# Phase_Measurements.net
KiCad netlist of a schematic drawn in Altium Designer
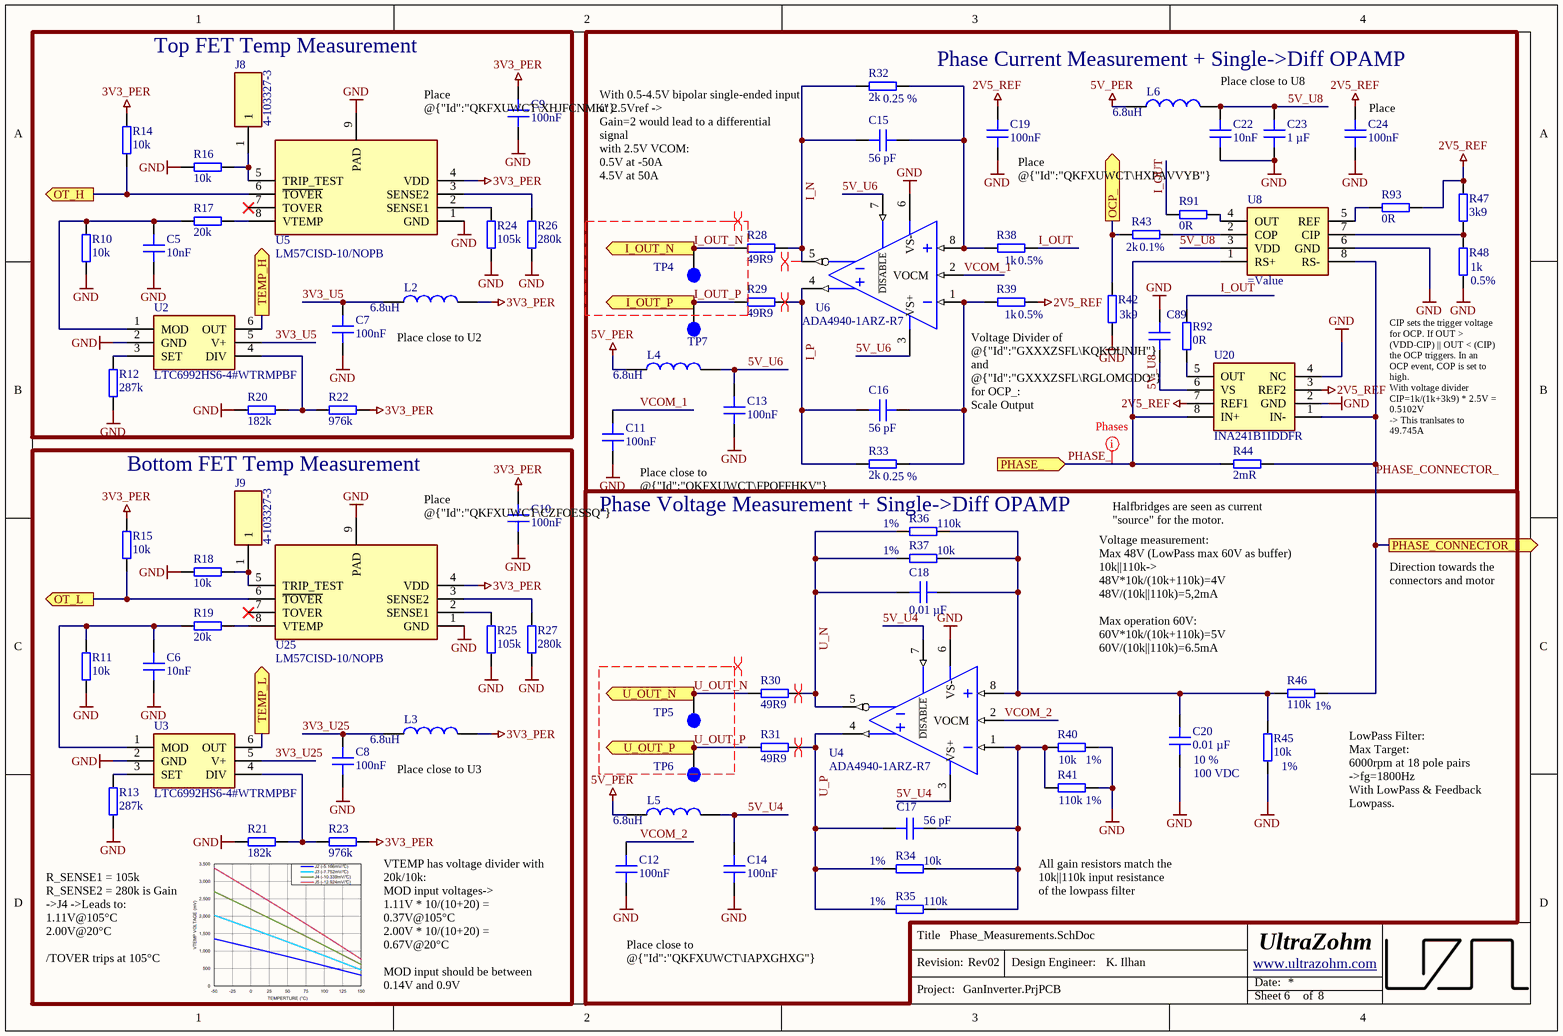
[diagram p0: Phase_Measurements.SchDoc]

(export (version "E")
  (design (tool "Eeschema 10.0.6"))
  (components
    (comp (ref "C5")
      (value "10nF")
      (footprint "C_0603")
      (description "50V 10nF 2X1 ±10%")
      (fields
        (field (name "MANUFACTURER PART NUMBER") "CT41G-0603-2X1-50V-0.01μF-K(N)")
        (field (name "MANUFACTURER") "TORCH")
        (field (name "CREATED FROM") "KIlhan")
      )
      (libsource (lib "user") (part "Capacitor"))
    )
    (comp (ref "C6")
      (value "10nF")
      (footprint "C_0603")
      (description "50V 10nF 2X1 ±10%")
      (fields
        (field (name "MANUFACTURER PART NUMBER") "CT41G-0603-2X1-50V-0.01μF-K(N)")
        (field (name "MANUFACTURER") "TORCH")
        (field (name "CREATED FROM") "KIlhan")
      )
      (libsource (lib "user") (part "Capacitor"))
    )
    (comp (ref "C7")
      (value "100nF")
      (footprint "C_0603")
      (description "50V 100nF X8R ±10% 0603")
      (fields
        (field (name "MANUFACTURER PART NUMBER") "CGA3E3X8R1H104KT0Y0N")
        (field (name "MANUFACTURER") "TDK")
        (field (name "CREATED FROM") "KIlhan")
      )
      (libsource (lib "user") (part "Capacitor"))
    )
    (comp (ref "C8")
      (value "100nF")
      (footprint "C_0603")
      (description "50V 100nF X8R ±10% 0603")
      (fields
        (field (name "MANUFACTURER PART NUMBER") "CGA3E3X8R1H104KT0Y0N")
        (field (name "MANUFACTURER") "TDK")
        (field (name "CREATED FROM") "KIlhan")
      )
      (libsource (lib "user") (part "Capacitor"))
    )
    (comp (ref "C9")
      (value "100nF")
      (footprint "C_0603")
      (description "50V 100nF X8R ±10% 0603")
      (fields
        (field (name "MANUFACTURER PART NUMBER") "CGA3E3X8R1H104KT0Y0N")
        (field (name "MANUFACTURER") "TDK")
        (field (name "CREATED FROM") "KIlhan")
      )
      (libsource (lib "user") (part "Capacitor"))
    )
    (comp (ref "C10")
      (value "100nF")
      (footprint "C_0603")
      (description "50V 100nF X8R ±10% 0603")
      (fields
        (field (name "MANUFACTURER PART NUMBER") "CGA3E3X8R1H104KT0Y0N")
        (field (name "MANUFACTURER") "TDK")
        (field (name "CREATED FROM") "KIlhan")
      )
      (libsource (lib "user") (part "Capacitor"))
    )
    (comp (ref "C11")
      (value "100nF")
      (footprint "C_0603")
      (description "50V 100nF X8R ±10% 0603")
      (fields
        (field (name "MANUFACTURER PART NUMBER") "CGA3E3X8R1H104KT0Y0N")
        (field (name "MANUFACTURER") "TDK")
        (field (name "CREATED FROM") "KIlhan")
      )
      (libsource (lib "user") (part "Capacitor"))
    )
    (comp (ref "C12")
      (value "100nF")
      (footprint "C_0603")
      (description "50V 100nF X8R ±10% 0603")
      (fields
        (field (name "MANUFACTURER PART NUMBER") "CGA3E3X8R1H104KT0Y0N")
        (field (name "MANUFACTURER") "TDK")
        (field (name "CREATED FROM") "KIlhan")
      )
      (libsource (lib "user") (part "Capacitor"))
    )
    (comp (ref "C13")
      (value "100nF")
      (footprint "C_0603")
      (description "50V 100nF X8R ±10% 0603")
      (fields
        (field (name "MANUFACTURER PART NUMBER") "CGA3E3X8R1H104KT0Y0N")
        (field (name "MANUFACTURER") "TDK")
        (field (name "CREATED FROM") "KIlhan")
      )
      (libsource (lib "user") (part "Capacitor"))
    )
    (comp (ref "C14")
      (value "100nF")
      (footprint "C_0603")
      (description "50V 100nF X8R ±10% 0603")
      (fields
        (field (name "MANUFACTURER PART NUMBER") "CGA3E3X8R1H104KT0Y0N")
        (field (name "MANUFACTURER") "TDK")
        (field (name "CREATED FROM") "KIlhan")
      )
      (libsource (lib "user") (part "Capacitor"))
    )
    (comp (ref "C15")
      (value "56 pF")
      (footprint "C_0603")
      (description "Capacitor 0603, 50 VDC, 56 pF, C0G")
      (fields
        (field (name "MANUFACTURER PART NUMBER") "CL10C560JB8NNNC")
        (field (name "MANUFACTURER") "Samsung Electro-Mechanics")
        (field (name "CREATED FROM") "DHufnagel")
      )
      (libsource (lib "user") (part "Capacitor"))
    )
    (comp (ref "C16")
      (value "56 pF")
      (footprint "C_0603")
      (description "Capacitor 0603, 50 VDC, 56 pF, C0G")
      (fields
        (field (name "MANUFACTURER PART NUMBER") "CL10C560JB8NNNC")
        (field (name "MANUFACTURER") "Samsung Electro-Mechanics")
        (field (name "CREATED FROM") "DHufnagel")
      )
      (libsource (lib "user") (part "Capacitor"))
    )
    (comp (ref "C17")
      (value "56 pF")
      (footprint "C_0603")
      (description "Capacitor 0603, 50 VDC, 56 pF, C0G")
      (fields
        (field (name "MANUFACTURER PART NUMBER") "CL10C560JB8NNNC")
        (field (name "MANUFACTURER") "Samsung Electro-Mechanics")
        (field (name "CREATED FROM") "DHufnagel")
      )
      (libsource (lib "user") (part "Capacitor"))
    )
    (comp (ref "C18")
      (value "0.01 µF")
      (footprint "C_0603")
      (description "25V 10nF C0G ±5% 0603 Multilayer Ceramic Capacitors MLCC - SMD/SMT ROHS")
      (fields
        (field (name "MANUFACTURER PART NUMBER") "C1608C0G1E103JT000N")
        (field (name "MANUFACTURER") "TDK")
        (field (name "CREATED FROM") "KIlhan")
      )
      (libsource (lib "user") (part "Capacitor"))
    )
    (comp (ref "C19")
      (value "100nF")
      (footprint "C_0603")
      (description "50V 100nF X8R ±10% 0603")
      (fields
        (field (name "MANUFACTURER PART NUMBER") "CGA3E3X8R1H104KT0Y0N")
        (field (name "MANUFACTURER") "TDK")
        (field (name "CREATED FROM") "KIlhan")
      )
      (libsource (lib "user") (part "Capacitor"))
    )
    (comp (ref "C20")
      (value "0.01 µF")
      (footprint "C_0805")
      (description "100V 10nF 0805 Multilayer Ceramic Capacitors MLCC - SMD/SMT ROHS")
      (fields
        (field (name "MANUFACTURER PART NUMBER") "HV0805X7R103K101NT")
        (field (name "MANUFACTURER") "AIDE")
        (field (name "TOLERANCE") "10 %")
        (field (name "VOLTAGE RATING") "100 VDC")
        (field (name "CREATED FROM") "KIlhan")
      )
      (libsource (lib "user") (part "Capacitor"))
    )
    (comp (ref "C22")
      (value "10nF")
      (footprint "C_0603")
      (description "50V 10nF 2X1 ±10%")
      (fields
        (field (name "MANUFACTURER PART NUMBER") "CT41G-0603-2X1-50V-0.01μF-K(N)")
        (field (name "MANUFACTURER") "TORCH")
        (field (name "CREATED FROM") "KIlhan")
      )
      (libsource (lib "user") (part "Capacitor"))
    )
    (comp (ref "C23")
      (value "1 µF")
      (footprint "C_0603")
      (description "50V 1uF X7R ±10% 0603 Multilayer Ceramic Capacitors MLCC - SMD/SMT ROHS")
      (fields
        (field (name "MANUFACTURER PART NUMBER") "UMK107AB7105KA-T")
        (field (name "MANUFACTURER") "Taiyo Yuden")
        (field (name "CREATED FROM") "NDiringer")
      )
      (libsource (lib "user") (part "Capacitor"))
    )
    (comp (ref "C24")
      (value "100nF")
      (footprint "C_0603")
      (description "50V 100nF X8R ±10% 0603")
      (fields
        (field (name "MANUFACTURER PART NUMBER") "CGA3E3X8R1H104KT0Y0N")
        (field (name "MANUFACTURER") "TDK")
        (field (name "CREATED FROM") "KIlhan")
      )
      (libsource (lib "user") (part "Capacitor"))
    )
    (comp (ref "C89")
      (value "100 nF")
      (footprint "C_0603")
      (description "Capacitor 0603, 50 VDC, 100 nF, X7R")
      (fields
        (field (name "MANUFACTURER PART NUMBER") "CC0603KRX7R9BB104")
        (field (name "MANUFACTURER") "YAGEO")
        (field (name "CREATED FROM") "AGeiger")
      )
      (libsource (lib "user") (part "Capacitor"))
    )
    (comp (ref "J8")
      (value "4-103327-3")
      (footprint "1_Pin_Header")
      (description "Pin Header, 2.54mm, 1 Pin")
      (fields
        (field (name "MANUFACTURER") "TE Connectivity")
        (field (name "LCSC PART NUMBER") "C3347196")
        (field (name "CREATED FROM") "DHufnagel")
      )
      (libsource (lib "user") (part "4-103327-3"))
    )
    (comp (ref "J9")
      (value "4-103327-3")
      (footprint "1_Pin_Header")
      (description "Pin Header, 2.54mm, 1 Pin")
      (fields
        (field (name "MANUFACTURER") "TE Connectivity")
        (field (name "LCSC PART NUMBER") "C3347196")
        (field (name "CREATED FROM") "DHufnagel")
      )
      (libsource (lib "user") (part "4-103327-3"))
    )
    (comp (ref "L2")
      (value "6.8uH")
      (footprint "INDC1608X95N")
      (description "6.8uH ±10% 0603 Inductors (SMD) ROHS")
      (fields
        (field (name "MF") "EPCOS / TDK")
        (field (name "MPN") "B82464G4154M")
        (field (name "CREATED FROM") "KIlhan")
      )
      (libsource (lib "user") (part "B82464G4154M"))
    )
    (comp (ref "L3")
      (value "6.8uH")
      (footprint "INDC1608X95N")
      (description "6.8uH ±10% 0603 Inductors (SMD) ROHS")
      (fields
        (field (name "MF") "EPCOS / TDK")
        (field (name "MPN") "B82464G4154M")
        (field (name "CREATED FROM") "KIlhan")
      )
      (libsource (lib "user") (part "B82464G4154M"))
    )
    (comp (ref "L4")
      (value "6.8uH")
      (footprint "INDC1608X95N")
      (description "6.8uH ±10% 0603 Inductors (SMD) ROHS")
      (fields
        (field (name "MF") "EPCOS / TDK")
        (field (name "MPN") "B82464G4154M")
        (field (name "CREATED FROM") "KIlhan")
      )
      (libsource (lib "user") (part "B82464G4154M"))
    )
    (comp (ref "L5")
      (value "6.8uH")
      (footprint "INDC1608X95N")
      (description "6.8uH ±10% 0603 Inductors (SMD) ROHS")
      (fields
        (field (name "MF") "EPCOS / TDK")
        (field (name "MPN") "B82464G4154M")
        (field (name "CREATED FROM") "KIlhan")
      )
      (libsource (lib "user") (part "B82464G4154M"))
    )
    (comp (ref "L6")
      (value "6.8uH")
      (footprint "INDC1608X95N")
      (description "6.8uH ±10% 0603 Inductors (SMD) ROHS")
      (fields
        (field (name "MF") "EPCOS / TDK")
        (field (name "MPN") "B82464G4154M")
        (field (name "CREATED FROM") "KIlhan")
      )
      (libsource (lib "user") (part "B82464G4154M"))
    )
    (comp (ref "R10")
      (value "10k")
      (footprint "RES 0603_1608")
      (description "SMD resistor E24 series")
      (fields
        (field (name "MANUFACTURER PART NUMBER") "RK73B1JTTD103J")
        (field (name "MANUFACTURER") "KOA Speer")
        (field (name "CREATED FROM") "MGremer")
      )
      (libsource (lib "user") (part "Resistor"))
    )
    (comp (ref "R11")
      (value "10k")
      (footprint "RES 0603_1608")
      (description "SMD resistor E24 series")
      (fields
        (field (name "MANUFACTURER PART NUMBER") "RK73B1JTTD103J")
        (field (name "MANUFACTURER") "KOA Speer")
        (field (name "CREATED FROM") "MGremer")
      )
      (libsource (lib "user") (part "Resistor"))
    )
    (comp (ref "R12")
      (value "287k")
      (footprint "RES 0805_2012")
      (description "SMD resistor 1%")
      (fields
        (field (name "MANUFACTURER PART NUMBER") "ERJ-6ENF2873V")
        (field (name "MANUFACTURER") "Panasonic")
        (field (name "CREATED FROM") "MGremer")
      )
      (libsource (lib "user") (part "Resistor"))
    )
    (comp (ref "R13")
      (value "287k")
      (footprint "RES 0805_2012")
      (description "SMD resistor 1%")
      (fields
        (field (name "MANUFACTURER PART NUMBER") "ERJ-6ENF2873V")
        (field (name "MANUFACTURER") "Panasonic")
        (field (name "CREATED FROM") "MGremer")
      )
      (libsource (lib "user") (part "Resistor"))
    )
    (comp (ref "R14")
      (value "10k")
      (footprint "RES 0603_1608")
      (description "SMD resistor E24 series")
      (fields
        (field (name "MANUFACTURER PART NUMBER") "RK73B1JTTD103J")
        (field (name "MANUFACTURER") "KOA Speer")
        (field (name "CREATED FROM") "MGremer")
      )
      (libsource (lib "user") (part "Resistor"))
    )
    (comp (ref "R15")
      (value "10k")
      (footprint "RES 0603_1608")
      (description "SMD resistor E24 series")
      (fields
        (field (name "MANUFACTURER PART NUMBER") "RK73B1JTTD103J")
        (field (name "MANUFACTURER") "KOA Speer")
        (field (name "CREATED FROM") "MGremer")
      )
      (libsource (lib "user") (part "Resistor"))
    )
    (comp (ref "R16")
      (value "10k")
      (footprint "RES 0603_1608")
      (description "SMD resistor E24 series")
      (fields
        (field (name "MANUFACTURER PART NUMBER") "RK73B1JTTD103J")
        (field (name "MANUFACTURER") "KOA Speer")
        (field (name "CREATED FROM") "MGremer")
      )
      (libsource (lib "user") (part "Resistor"))
    )
    (comp (ref "R17")
      (value "20k")
      (footprint "RES 0603_1608")
      (description "SMD resistor E24 series")
      (fields
        (field (name "MANUFACTURER PART NUMBER") "0603WAF2002T5E")
        (field (name "MANUFACTURER") "UNI-ROYAL")
        (field (name "CREATED FROM") "AGeiger")
      )
      (libsource (lib "user") (part "Resistor"))
    )
    (comp (ref "R18")
      (value "10k")
      (footprint "RES 0603_1608")
      (description "SMD resistor E24 series")
      (fields
        (field (name "MANUFACTURER PART NUMBER") "RK73B1JTTD103J")
        (field (name "MANUFACTURER") "KOA Speer")
        (field (name "CREATED FROM") "MGremer")
      )
      (libsource (lib "user") (part "Resistor"))
    )
    (comp (ref "R19")
      (value "20k")
      (footprint "RES 0603_1608")
      (description "SMD resistor E24 series")
      (fields
        (field (name "MANUFACTURER PART NUMBER") "0603WAF2002T5E")
        (field (name "MANUFACTURER") "UNI-ROYAL")
        (field (name "CREATED FROM") "AGeiger")
      )
      (libsource (lib "user") (part "Resistor"))
    )
    (comp (ref "R20")
      (value "182k")
      (footprint "RES 0603_1608")
      (description "SMD resistor 1%, 50V, 100ppm")
      (fields
        (field (name "MANUFACTURER PART NUMBER") "CR0603-FX-1823ELF")
        (field (name "MANUFACTURER") "Bourns")
        (field (name "CREATED FROM") "DHufnagel")
      )
      (libsource (lib "user") (part "Resistor"))
    )
    (comp (ref "R21")
      (value "182k")
      (footprint "RES 0603_1608")
      (description "SMD resistor 1%, 50V, 100ppm")
      (fields
        (field (name "MANUFACTURER PART NUMBER") "CR0603-FX-1823ELF")
        (field (name "MANUFACTURER") "Bourns")
        (field (name "CREATED FROM") "DHufnagel")
      )
      (libsource (lib "user") (part "Resistor"))
    )
    (comp (ref "R22")
      (value "976k")
      (footprint "RES 0603_1608")
      (description "SMD resistor 1%, 50V, 100ppm")
      (fields
        (field (name "MANUFACTURER PART NUMBER") "CR0603-FX-9763ELF")
        (field (name "MANUFACTURER") "Bourns")
        (field (name "CREATED FROM") "DHufnagel")
      )
      (libsource (lib "user") (part "Resistor"))
    )
    (comp (ref "R23")
      (value "976k")
      (footprint "RES 0603_1608")
      (description "SMD resistor 1%, 50V, 100ppm")
      (fields
        (field (name "MANUFACTURER PART NUMBER") "CR0603-FX-9763ELF")
        (field (name "MANUFACTURER") "Bourns")
        (field (name "CREATED FROM") "DHufnagel")
      )
      (libsource (lib "user") (part "Resistor"))
    )
    (comp (ref "R24")
      (value "105k")
      (footprint "RES 0603_1608")
      (description "100mW Thick Film Resistors ±100ppm/℃ ±1% 105kΩ 0603 Chip Resistor - Surface Mount ROHS")
      (fields
        (field (name "MANUFACTURER PART NUMBER") "RC0603FR-07105KL")
        (field (name "MANUFACTURER") "YAGEO")
        (field (name "CREATED FROM") "KIlhan")
      )
      (libsource (lib "user") (part "Resistor"))
    )
    (comp (ref "R25")
      (value "105k")
      (footprint "RES 0603_1608")
      (description "100mW Thick Film Resistors ±100ppm/℃ ±1% 105kΩ 0603 Chip Resistor - Surface Mount ROHS")
      (fields
        (field (name "MANUFACTURER PART NUMBER") "RC0603FR-07105KL")
        (field (name "MANUFACTURER") "YAGEO")
        (field (name "CREATED FROM") "KIlhan")
      )
      (libsource (lib "user") (part "Resistor"))
    )
    (comp (ref "R26")
      (value "280k")
      (footprint "RES 0603_1608")
      (description "100mW Thin Film Resistor ±50ppm/℃ ±0.1% 280kΩ 0603 Chip Resistor - Surface Mount ROHS")
      (fields
        (field (name "MANUFACTURER PART NUMBER") "RT0603BRE07280KL")
        (field (name "MANUFACTURER") "YAGEO")
        (field (name "CREATED FROM") "KIlhan")
      )
      (libsource (lib "user") (part "Resistor"))
    )
    (comp (ref "R27")
      (value "280k")
      (footprint "RES 0603_1608")
      (description "100mW Thin Film Resistor ±50ppm/℃ ±0.1% 280kΩ 0603 Chip Resistor - Surface Mount ROHS")
      (fields
        (field (name "MANUFACTURER PART NUMBER") "RT0603BRE07280KL")
        (field (name "MANUFACTURER") "YAGEO")
        (field (name "CREATED FROM") "KIlhan")
      )
      (libsource (lib "user") (part "Resistor"))
    )
    (comp (ref "R28")
      (value "49R9")
      (footprint "RES 0603_1608")
      (description "125mW Thin Film Resistor ±0.1% ±25ppm/℃ 49.9Ω 0603")
      (fields
        (field (name "MANUFACTURER PART NUMBER") "TNPW060349R9BEEA")
        (field (name "MANUFACTURER") "Vishay Intertech")
        (field (name "CREATED FROM") "KIlhan")
      )
      (libsource (lib "user") (part "Resistor"))
    )
    (comp (ref "R29")
      (value "49R9")
      (footprint "RES 0603_1608")
      (description "125mW Thin Film Resistor ±0.1% ±25ppm/℃ 49.9Ω 0603")
      (fields
        (field (name "MANUFACTURER PART NUMBER") "TNPW060349R9BEEA")
        (field (name "MANUFACTURER") "Vishay Intertech")
        (field (name "CREATED FROM") "KIlhan")
      )
      (libsource (lib "user") (part "Resistor"))
    )
    (comp (ref "R30")
      (value "49R9")
      (footprint "RES 0603_1608")
      (description "125mW Thin Film Resistor ±0.1% ±25ppm/℃ 49.9Ω 0603")
      (fields
        (field (name "MANUFACTURER PART NUMBER") "TNPW060349R9BEEA")
        (field (name "MANUFACTURER") "Vishay Intertech")
        (field (name "CREATED FROM") "KIlhan")
      )
      (libsource (lib "user") (part "Resistor"))
    )
    (comp (ref "R31")
      (value "49R9")
      (footprint "RES 0603_1608")
      (description "125mW Thin Film Resistor ±0.1% ±25ppm/℃ 49.9Ω 0603")
      (fields
        (field (name "MANUFACTURER PART NUMBER") "TNPW060349R9BEEA")
        (field (name "MANUFACTURER") "Vishay Intertech")
        (field (name "CREATED FROM") "KIlhan")
      )
      (libsource (lib "user") (part "Resistor"))
    )
    (comp (ref "R32")
      (value "2k")
      (footprint "RES 0603_1608")
      (description "100mW Thin Film Resistor ±50ppm/℃ ±0.25% 2kΩ 0603 Chip Resistor - Surface Mount ROHS")
      (fields
        (field (name "MANUFACTURER PART NUMBER") "RT0603CRE072KL")
        (field (name "MANUFACTURER") "YAGEO")
        (field (name "TOLERANCE") "0.25 %")
        (field (name "CREATED FROM") "KIlhan")
      )
      (libsource (lib "user") (part "Resistor"))
    )
    (comp (ref "R33")
      (value "2k")
      (footprint "RES 0603_1608")
      (description "100mW Thin Film Resistor ±50ppm/℃ ±0.25% 2kΩ 0603 Chip Resistor - Surface Mount ROHS")
      (fields
        (field (name "MANUFACTURER PART NUMBER") "RT0603CRE072KL")
        (field (name "MANUFACTURER") "YAGEO")
        (field (name "TOLERANCE") "0.25 %")
        (field (name "CREATED FROM") "KIlhan")
      )
      (libsource (lib "user") (part "Resistor"))
    )
    (comp (ref "R34")
      (value "10k")
      (footprint "RES 0603_1608")
      (description "SMD resistor 1%")
      (fields
        (field (name "MANUFACTURER PART NUMBER") "0603WAF1002T5E")
        (field (name "MANUFACTURER") "UNI-ROYAL")
        (field (name "TOLERANCE") "1%")
        (field (name "CREATED FROM") "AGeiger")
      )
      (libsource (lib "user") (part "Resistor"))
    )
    (comp (ref "R35")
      (value "110k")
      (footprint "RES 0603_1608")
      (description "100mW Thick Film Resistors ±100ppm/℃ ±1% 110kΩ 0603 Chip Resistor - Surface Mount ROHS")
      (fields
        (field (name "MANUFACTURER PART NUMBER") "WR06X1103FTL")
        (field (name "MANUFACTURER") "Walsin Tech Corp")
        (field (name "TOLERANCE") "1%")
        (field (name "CREATED FROM") "KIlhan")
      )
      (libsource (lib "user") (part "Resistor"))
    )
    (comp (ref "R36")
      (value "110k")
      (footprint "RES 0603_1608")
      (description "100mW Thick Film Resistors ±100ppm/℃ ±1% 110kΩ 0603 Chip Resistor - Surface Mount ROHS")
      (fields
        (field (name "MANUFACTURER PART NUMBER") "WR06X1103FTL")
        (field (name "MANUFACTURER") "Walsin Tech Corp")
        (field (name "TOLERANCE") "1%")
        (field (name "CREATED FROM") "KIlhan")
      )
      (libsource (lib "user") (part "Resistor"))
    )
    (comp (ref "R37")
      (value "10k")
      (footprint "RES 0603_1608")
      (description "SMD resistor 1%")
      (fields
        (field (name "MANUFACTURER PART NUMBER") "0603WAF1002T5E")
        (field (name "MANUFACTURER") "UNI-ROYAL")
        (field (name "TOLERANCE") "1%")
        (field (name "CREATED FROM") "AGeiger")
      )
      (libsource (lib "user") (part "Resistor"))
    )
    (comp (ref "R38")
      (value "1k")
      (footprint "RES 0603_1608")
      (description "SMD resistor E24 series 470 kOhms 100-200 mW 0603 1%")
      (fields
        (field (name "MANUFACTURER PART NUMBER") "0603WAD1001T5E")
        (field (name "MANUFACTURER") "UNI-ROYAL(Uniroyal Elec)")
        (field (name "TOLERANCE") "0.5%")
        (field (name "CREATED FROM") "NDiringer")
      )
      (libsource (lib "user") (part "Resistor"))
    )
    (comp (ref "R39")
      (value "1k")
      (footprint "RES 0603_1608")
      (description "SMD resistor E24 series 470 kOhms 100-200 mW 0603 1%")
      (fields
        (field (name "MANUFACTURER PART NUMBER") "0603WAD1001T5E")
        (field (name "MANUFACTURER") "UNI-ROYAL(Uniroyal Elec)")
        (field (name "TOLERANCE") "0.5%")
        (field (name "CREATED FROM") "NDiringer")
      )
      (libsource (lib "user") (part "Resistor"))
    )
    (comp (ref "R40")
      (value "10k")
      (footprint "RES 0603_1608")
      (description "SMD resistor 1%")
      (fields
        (field (name "MANUFACTURER PART NUMBER") "0603WAF1002T5E")
        (field (name "MANUFACTURER") "UNI-ROYAL")
        (field (name "TOLERANCE") "1%")
        (field (name "CREATED FROM") "AGeiger")
      )
      (libsource (lib "user") (part "Resistor"))
    )
    (comp (ref "R41")
      (value "110k")
      (footprint "RES 0603_1608")
      (description "100mW Thick Film Resistors ±100ppm/℃ ±1% 110kΩ 0603 Chip Resistor - Surface Mount ROHS")
      (fields
        (field (name "MANUFACTURER PART NUMBER") "WR06X1103FTL")
        (field (name "MANUFACTURER") "Walsin Tech Corp")
        (field (name "TOLERANCE") "1%")
        (field (name "CREATED FROM") "KIlhan")
      )
      (libsource (lib "user") (part "Resistor"))
    )
    (comp (ref "R42")
      (value "3k9")
      (footprint "RES 0603_1608")
      (description "SMD resistor E24 series")
      (fields
        (field (name "MANUFACTURER PART NUMBER") "RT0603FRE073K9L")
        (field (name "MANUFACTURER") "YAGEO")
        (field (name "CREATED FROM") "DHufnagel")
      )
      (libsource (lib "user") (part "Resistor"))
    )
    (comp (ref "R43")
      (value "2k")
      (footprint "RES 0603_1608")
      (description "SMD resistor 0.1%")
      (fields
        (field (name "MANUFACTURER PART NUMBER") "ERJ-PB3B2001V")
        (field (name "MANUFACTURER") "Panasonic")
        (field (name "TOLERANCE") "0.1%")
        (field (name "CREATED FROM") "DHufnagel")
      )
      (libsource (lib "user") (part "Resistor"))
    )
    (comp (ref "R44")
      (value "2mR")
      (footprint "3921")
      (description "Shunt resistor 2mOhm, 5W, 1%")
      (fields
        (field (name "MANUFACTURER PART NUMBER") "PU3921FKMP50R002L")
        (field (name "MANUFACTURER") "YAGEO")
        (field (name "CREATED FROM") "DHufnagel")
      )
      (libsource (lib "user") (part "Resistor"))
    )
    (comp (ref "R45")
      (value "10k")
      (footprint "RES 0603_1608")
      (description "SMD resistor 1%")
      (fields
        (field (name "MANUFACTURER PART NUMBER") "0603WAF1002T5E")
        (field (name "MANUFACTURER") "UNI-ROYAL")
        (field (name "TOLERANCE") "1%")
        (field (name "CREATED FROM") "AGeiger")
      )
      (libsource (lib "user") (part "Resistor"))
    )
    (comp (ref "R46")
      (value "110k")
      (footprint "RES 0603_1608")
      (description "100mW Thick Film Resistors ±100ppm/℃ ±1% 110kΩ 0603 Chip Resistor - Surface Mount ROHS")
      (fields
        (field (name "MANUFACTURER PART NUMBER") "WR06X1103FTL")
        (field (name "MANUFACTURER") "Walsin Tech Corp")
        (field (name "TOLERANCE") "1%")
        (field (name "CREATED FROM") "KIlhan")
      )
      (libsource (lib "user") (part "Resistor"))
    )
    (comp (ref "R47")
      (value "3k9")
      (footprint "RES 0603_1608")
      (description "SMD resistor E24 series")
      (fields
        (field (name "MANUFACTURER PART NUMBER") "RT0603FRE073K9L")
        (field (name "MANUFACTURER") "YAGEO")
        (field (name "CREATED FROM") "DHufnagel")
      )
      (libsource (lib "user") (part "Resistor"))
    )
    (comp (ref "R48")
      (value "1k")
      (footprint "RES 0603_1608")
      (description "SMD resistor E24 series 470 kOhms 100-200 mW 0603 1%")
      (fields
        (field (name "MANUFACTURER PART NUMBER") "0603WAD1001T5E")
        (field (name "MANUFACTURER") "UNI-ROYAL(Uniroyal Elec)")
        (field (name "TOLERANCE") "0.5%")
        (field (name "CREATED FROM") "NDiringer")
      )
      (libsource (lib "user") (part "Resistor"))
    )
    (comp (ref "R91")
      (value "0R")
      (footprint "RES 0603_1608")
      (description "SMD resistor E24 series")
      (fields
        (field (name "MANUFACTURER PART NUMBER") "RC0603JR-070RL")
        (field (name "MANUFACTURER") "YAGEO")
        (field (name "CREATED FROM") "MGremer")
      )
      (libsource (lib "user") (part "Resistor"))
    )
    (comp (ref "R92")
      (value "0R")
      (footprint "RES 0603_1608")
      (description "SMD resistor E24 series")
      (fields
        (field (name "MANUFACTURER PART NUMBER") "RC0603JR-070RL")
        (field (name "MANUFACTURER") "YAGEO")
        (field (name "CREATED FROM") "MGremer")
      )
      (libsource (lib "user") (part "Resistor"))
    )
    (comp (ref "R93")
      (value "0R")
      (footprint "RES 0603_1608")
      (description "SMD resistor E24 series")
      (fields
        (field (name "MANUFACTURER PART NUMBER") "RC0603JR-070RL")
        (field (name "MANUFACTURER") "YAGEO")
        (field (name "CREATED FROM") "MGremer")
      )
      (libsource (lib "user") (part "Resistor"))
    )
    (comp (ref "TP4")
      (value "Testpoint 1mm")
      (footprint "TP_1mm")
      (fields
        (field (name "MANUFACTURER PART NUMBER") "NULL")
        (field (name "CREATED") "2018_06_25_AGeiger")
        (field (name "CREATED FROM") "AGeiger")
      )
      (libsource (lib "user") (part "TP_1mm"))
    )
    (comp (ref "TP5")
      (value "Testpoint 1mm")
      (footprint "TP_1mm")
      (fields
        (field (name "MANUFACTURER PART NUMBER") "NULL")
        (field (name "CREATED") "2018_06_25_AGeiger")
        (field (name "CREATED FROM") "AGeiger")
      )
      (libsource (lib "user") (part "TP_1mm"))
    )
    (comp (ref "TP6")
      (value "Testpoint 1mm")
      (footprint "TP_1mm")
      (fields
        (field (name "MANUFACTURER PART NUMBER") "NULL")
        (field (name "CREATED") "2018_06_25_AGeiger")
        (field (name "CREATED FROM") "AGeiger")
      )
      (libsource (lib "user") (part "TP_1mm"))
    )
    (comp (ref "TP7")
      (value "Testpoint 1mm")
      (footprint "TP_1mm")
      (fields
        (field (name "MANUFACTURER PART NUMBER") "NULL")
        (field (name "CREATED") "2018_06_25_AGeiger")
        (field (name "CREATED FROM") "AGeiger")
      )
      (libsource (lib "user") (part "TP_1mm"))
    )
    (comp (ref "U2")
      (value "LTC6992HS6-4#WTRMPBF")
      (footprint "SOT95P280X100-6N")
      (description "Switching Controllers PWM with 5% to 100% Pulse Width Control")
      (fields
        (field (name "MANUFACTURER") "Analog Devices")
        (field (name "LCSC PART NUMBER") "C3304518")
        (field (name "CREATED FROM") "DHufnagel")
      )
      (libsource (lib "user") (part "LTC6992HS6-4#WTRMPBF"))
    )
    (comp (ref "U3")
      (value "LTC6992HS6-4#WTRMPBF")
      (footprint "SOT95P280X100-6N")
      (description "Switching Controllers PWM with 5% to 100% Pulse Width Control")
      (fields
        (field (name "MANUFACTURER") "Analog Devices")
        (field (name "LCSC PART NUMBER") "C3304518")
        (field (name "CREATED FROM") "DHufnagel")
      )
      (libsource (lib "user") (part "LTC6992HS6-4#WTRMPBF"))
    )
    (comp (ref "U4")
      (value "ADA4940-1ARZ-R7")
      (footprint "SOT127P600X175-8N")
      (description "Fully Differential Amplifier, Ultralow-Power,Low Distortion, 260-MHz")
      (fields
        (field (name "MANUFACTURER") "Analog Devices")
        (field (name "LCSC PART NUMBER") "C730049")
        (field (name "CREATED FROM") "DHufnagel")
      )
      (libsource (lib "user") (part "ADA4940-1ARZ"))
    )
    (comp (ref "U5")
      (value "LM57CISD-10/NOPB")
      (footprint "SON50P250X250X80-9N")
      (description "Board Mount Temperature Sensor, -50 - 150°C")
      (fields
        (field (name "MANUFACTURER") "Texas Instruments")
        (field (name "LCSC PART NUMBER") "C2864091")
        (field (name "CREATED FROM") "DHufnagel")
      )
      (libsource (lib "user") (part "LM57CISD-10_NOPB"))
    )
    (comp (ref "U6")
      (value "ADA4940-1ARZ-R7")
      (footprint "SOT127P600X175-8N")
      (description "Fully Differential Amplifier, Ultralow-Power,Low Distortion, 260-MHz")
      (fields
        (field (name "MANUFACTURER") "Analog Devices")
        (field (name "LCSC PART NUMBER") "C730049")
        (field (name "CREATED FROM") "DHufnagel")
      )
      (libsource (lib "user") (part "ADA4940-1ARZ"))
    )
    (comp (ref "U8")
      (value "~")
      (footprint "SOP65P490X110-8N")
      (description "Current Sense Amplifier, 300kHz, -0.1V to 65V CMV, 2 Channel")
      (fields
        (field (name "MANUFACTURER_PART_NUMBER") "MAX40056TAUA+")
        (field (name "MOUSER PART NUMBER") "700-MAX40056TAUA+")
        (field (name "CREATED FROM") "KIlhan")
      )
      (libsource (lib "user") (part "MAX40056TAUA+"))
    )
    (comp (ref "U20")
      (value "INA241B1IDDFR")
      (footprint "SOT65P280X110-8N")
      (fields
        (field (name "MOUSER PART NUMBER") "595-INA241B1IDDFR")
        (field (name "LCSC PART NUMBER") "C7433256")
        (field (name "MANUFACTURER") "Texas Instruments")
        (field (name "CREATED FROM") "KIlhan")
      )
      (libsource (lib "user") (part "INA241B1IDDFR"))
    )
    (comp (ref "U25")
      (value "LM57CISD-10/NOPB")
      (footprint "SON50P250X250X80-9N")
      (description "Board Mount Temperature Sensor, -50 - 150°C")
      (fields
        (field (name "MANUFACTURER") "Texas Instruments")
        (field (name "LCSC PART NUMBER") "C2864091")
        (field (name "CREATED FROM") "DHufnagel")
      )
      (libsource (lib "user") (part "LM57CISD-10_NOPB"))
    )
  )
  (nets
    (net (code "1") (name "/3V3_U5") (class "Default")
      (node (ref "C7") (pin "2") (pinfunction "2_2") (pintype "passive"))
      (node (ref "L2") (pin "1") (pinfunction "1_1") (pintype "passive"))
      (node (ref "U2") (pin "5") (pinfunction "V+_5") (pintype "passive"))
    )
    (net (code "2") (name "/3V3_U25") (class "Default")
      (node (ref "C8") (pin "2") (pinfunction "2_2") (pintype "passive"))
      (node (ref "L3") (pin "1") (pinfunction "1_1") (pintype "passive"))
      (node (ref "U3") (pin "5") (pinfunction "V+_5") (pintype "passive"))
    )
    (net (code "3") (name "/5V_U4") (class "Default")
      (node (ref "C14") (pin "2") (pinfunction "2_2") (pintype "passive"))
      (node (ref "L5") (pin "2") (pinfunction "2_2") (pintype "passive"))
      (node (ref "U4") (pin "3") (pinfunction "VS+_3") (pintype "power_in"))
      (node (ref "U4") (pin "7") (pinfunction "~{DISABLE}_7") (pintype "input"))
    )
    (net (code "4") (name "/5V_U6") (class "Default")
      (node (ref "C13") (pin "2") (pinfunction "2_2") (pintype "passive"))
      (node (ref "L4") (pin "2") (pinfunction "2_2") (pintype "passive"))
      (node (ref "U6") (pin "3") (pinfunction "VS+_3") (pintype "power_in"))
      (node (ref "U6") (pin "7") (pinfunction "~{DISABLE}_7") (pintype "input"))
    )
    (net (code "5") (name "/5V_U8") (class "Default")
      (node (ref "C22") (pin "2") (pinfunction "2_2") (pintype "passive"))
      (node (ref "C23") (pin "2") (pinfunction "2_2") (pintype "passive"))
      (node (ref "C89") (pin "2") (pinfunction "2_2") (pintype "passive"))
      (node (ref "L6") (pin "2") (pinfunction "2_2") (pintype "passive"))
      (node (ref "U20") (pin "6") (pinfunction "VS_6") (pintype "passive"))
      (node (ref "U8") (pin "3") (pinfunction "VDD_3") (pintype "passive"))
    )
    (net (code "6") (name "/I_N") (class "Default")
      (node (ref "C15") (pin "1") (pinfunction "1_1") (pintype "passive"))
      (node (ref "R28") (pin "2") (pinfunction "2_2") (pintype "passive"))
      (node (ref "R32") (pin "1") (pinfunction "1_1") (pintype "passive"))
      (node (ref "U6") (pin "5") (pinfunction "VOUT-_5") (pintype "output"))
    )
    (net (code "7") (name "/I_OUT") (class "Default")
      (node (ref "R38") (pin "2") (pinfunction "2_2") (pintype "passive"))
      (node (ref "R91") (pin "1") (pinfunction "1_1") (pintype "passive"))
      (node (ref "R92") (pin "2") (pinfunction "2_2") (pintype "passive"))
    )
    (net (code "8") (name "/I_OUT_N") (class "Default")
      (node (ref "R28") (pin "1") (pinfunction "1_1") (pintype "passive"))
      (node (ref "TP4") (pin "1") (pintype "passive"))
    )
    (net (code "9") (name "/I_OUT_P") (class "Default")
      (node (ref "R29") (pin "1") (pinfunction "1_1") (pintype "passive"))
      (node (ref "TP7") (pin "1") (pintype "passive"))
    )
    (net (code "10") (name "/I_P") (class "Default")
      (node (ref "C16") (pin "1") (pinfunction "1_1") (pintype "passive"))
      (node (ref "R29") (pin "2") (pinfunction "2_2") (pintype "passive"))
      (node (ref "R33") (pin "1") (pinfunction "1_1") (pintype "passive"))
      (node (ref "U6") (pin "4") (pinfunction "VOUT+_4") (pintype "output"))
    )
    (net (code "11") (name "/OCP_") (class "Default")
      (node (ref "R42") (pin "1") (pinfunction "1_1") (pintype "passive"))
      (node (ref "R43") (pin "1") (pinfunction "1_1") (pintype "passive"))
    )
    (net (code "12") (name "/OT_H") (class "Default")
      (node (ref "R14") (pin "2") (pinfunction "2_2") (pintype "passive"))
      (node (ref "U5") (pin "6") (pinfunction "~{TOVER}_6") (pintype "passive"))
    )
    (net (code "13") (name "/OT_L") (class "Default")
      (node (ref "R15") (pin "2") (pinfunction "2_2") (pintype "passive"))
      (node (ref "U25") (pin "6") (pinfunction "~{TOVER}_6") (pintype "passive"))
    )
    (net (code "14") (name "/PHASE_") (class "Default")
      (node (ref "R44") (pin "1") (pinfunction "1_1") (pintype "passive"))
      (node (ref "U20") (pin "8") (pinfunction "IN+_8") (pintype "passive"))
      (node (ref "U8") (pin "1") (pinfunction "RS+_1") (pintype "passive"))
    )
    (net (code "15") (name "/PHASE_CONNECTOR_") (class "Default")
      (node (ref "R44") (pin "2") (pinfunction "2_2") (pintype "passive"))
      (node (ref "R46") (pin "2") (pinfunction "2_2") (pintype "passive"))
      (node (ref "U20") (pin "1") (pinfunction "IN-_1") (pintype "passive"))
      (node (ref "U8") (pin "8") (pinfunction "RS-_8") (pintype "passive"))
    )
    (net (code "16") (name "/TEMP_H") (class "Default")
      (node (ref "U2") (pin "6") (pinfunction "OUT_6") (pintype "passive"))
    )
    (net (code "17") (name "/TEMP_L") (class "Default")
      (node (ref "U3") (pin "6") (pinfunction "OUT_6") (pintype "passive"))
    )
    (net (code "18") (name "/U_N") (class "Default")
      (node (ref "C18") (pin "1") (pinfunction "1_1") (pintype "passive"))
      (node (ref "R30") (pin "2") (pinfunction "2_2") (pintype "passive"))
      (node (ref "R36") (pin "1") (pinfunction "1_1") (pintype "passive"))
      (node (ref "R37") (pin "2") (pinfunction "2_2") (pintype "passive"))
      (node (ref "U4") (pin "5") (pinfunction "VOUT-_5") (pintype "output"))
    )
    (net (code "19") (name "/U_OUT_N") (class "Default")
      (node (ref "R30") (pin "1") (pinfunction "1_1") (pintype "passive"))
      (node (ref "TP5") (pin "1") (pintype "passive"))
    )
    (net (code "20") (name "/U_OUT_P") (class "Default")
      (node (ref "R31") (pin "1") (pinfunction "1_1") (pintype "passive"))
      (node (ref "TP6") (pin "1") (pintype "passive"))
    )
    (net (code "21") (name "/U_P") (class "Default")
      (node (ref "C17") (pin "1") (pinfunction "1_1") (pintype "passive"))
      (node (ref "R31") (pin "2") (pinfunction "2_2") (pintype "passive"))
      (node (ref "R34") (pin "2") (pinfunction "2_2") (pintype "passive"))
      (node (ref "R35") (pin "1") (pinfunction "1_1") (pintype "passive"))
      (node (ref "U4") (pin "4") (pinfunction "VOUT+_4") (pintype "output"))
    )
    (net (code "22") (name "/VCOM_1") (class "Default")
      (node (ref "C11") (pin "2") (pinfunction "2_2") (pintype "passive"))
      (node (ref "U6") (pin "2") (pinfunction "VOCM_2") (pintype "input"))
    )
    (net (code "23") (name "/VCOM_2") (class "Default")
      (node (ref "C12") (pin "2") (pinfunction "2_2") (pintype "passive"))
      (node (ref "U4") (pin "2") (pinfunction "VOCM_2") (pintype "input"))
    )
    (net (code "24") (name "2V5_REF") (class "Default")
      (node (ref "C19") (pin "1") (pinfunction "1_1") (pintype "passive"))
      (node (ref "C24") (pin "1") (pinfunction "1_1") (pintype "passive"))
      (node (ref "R39") (pin "2") (pinfunction "2_2") (pintype "passive"))
      (node (ref "R47") (pin "2") (pinfunction "2_2") (pintype "passive"))
      (node (ref "R93") (pin "2") (pinfunction "2_2") (pintype "passive"))
      (node (ref "U20") (pin "3") (pinfunction "REF2_3") (pintype "passive"))
      (node (ref "U20") (pin "7") (pinfunction "REF1_7") (pintype "passive"))
    )
    (net (code "25") (name "3V3_PER") (class "Default")
      (node (ref "C10") (pin "1") (pinfunction "1_1") (pintype "passive"))
      (node (ref "C9") (pin "1") (pinfunction "1_1") (pintype "passive"))
      (node (ref "L2") (pin "2") (pinfunction "2_2") (pintype "passive"))
      (node (ref "L3") (pin "2") (pinfunction "2_2") (pintype "passive"))
      (node (ref "R14") (pin "1") (pinfunction "1_1") (pintype "passive"))
      (node (ref "R15") (pin "1") (pinfunction "1_1") (pintype "passive"))
      (node (ref "R22") (pin "2") (pinfunction "2_2") (pintype "passive"))
      (node (ref "R23") (pin "2") (pinfunction "2_2") (pintype "passive"))
      (node (ref "U25") (pin "4") (pinfunction "VDD_4") (pintype "passive"))
      (node (ref "U5") (pin "4") (pinfunction "VDD_4") (pintype "passive"))
    )
    (net (code "26") (name "5V_PER") (class "Default")
      (node (ref "L4") (pin "1") (pinfunction "1_1") (pintype "passive"))
      (node (ref "L5") (pin "1") (pinfunction "1_1") (pintype "passive"))
      (node (ref "L6") (pin "1") (pinfunction "1_1") (pintype "passive"))
    )
    (net (code "27") (name "GND") (class "Default")
      (node (ref "C10") (pin "2") (pinfunction "2_2") (pintype "passive"))
      (node (ref "C11") (pin "1") (pinfunction "1_1") (pintype "passive"))
      (node (ref "C12") (pin "1") (pinfunction "1_1") (pintype "passive"))
      (node (ref "C13") (pin "1") (pinfunction "1_1") (pintype "passive"))
      (node (ref "C14") (pin "1") (pinfunction "1_1") (pintype "passive"))
      (node (ref "C19") (pin "2") (pinfunction "2_2") (pintype "passive"))
      (node (ref "C20") (pin "1") (pinfunction "1_1") (pintype "passive"))
      (node (ref "C22") (pin "1") (pinfunction "1_1") (pintype "passive"))
      (node (ref "C23") (pin "1") (pinfunction "1_1") (pintype "passive"))
      (node (ref "C24") (pin "2") (pinfunction "2_2") (pintype "passive"))
      (node (ref "C5") (pin "1") (pinfunction "1_1") (pintype "passive"))
      (node (ref "C6") (pin "1") (pinfunction "1_1") (pintype "passive"))
      (node (ref "C7") (pin "1") (pinfunction "1_1") (pintype "passive"))
      (node (ref "C8") (pin "1") (pinfunction "1_1") (pintype "passive"))
      (node (ref "C89") (pin "1") (pinfunction "1_1") (pintype "passive"))
      (node (ref "C9") (pin "2") (pinfunction "2_2") (pintype "passive"))
      (node (ref "R10") (pin "2") (pinfunction "2_2") (pintype "passive"))
      (node (ref "R11") (pin "2") (pinfunction "2_2") (pintype "passive"))
      (node (ref "R12") (pin "1") (pinfunction "1_1") (pintype "passive"))
      (node (ref "R13") (pin "1") (pinfunction "1_1") (pintype "passive"))
      (node (ref "R16") (pin "2") (pinfunction "2_2") (pintype "passive"))
      (node (ref "R18") (pin "2") (pinfunction "2_2") (pintype "passive"))
      (node (ref "R20") (pin "1") (pinfunction "1_1") (pintype "passive"))
      (node (ref "R21") (pin "1") (pinfunction "1_1") (pintype "passive"))
      (node (ref "R24") (pin "1") (pinfunction "1_1") (pintype "passive"))
      (node (ref "R25") (pin "1") (pinfunction "1_1") (pintype "passive"))
      (node (ref "R26") (pin "1") (pinfunction "1_1") (pintype "passive"))
      (node (ref "R27") (pin "1") (pinfunction "1_1") (pintype "passive"))
      (node (ref "R40") (pin "1") (pinfunction "1_1") (pintype "passive"))
      (node (ref "R41") (pin "2") (pinfunction "2_2") (pintype "passive"))
      (node (ref "R42") (pin "2") (pinfunction "2_2") (pintype "passive"))
      (node (ref "R45") (pin "1") (pinfunction "1_1") (pintype "passive"))
      (node (ref "R48") (pin "1") (pinfunction "1_1") (pintype "passive"))
      (node (ref "U2") (pin "2") (pinfunction "GND_2") (pintype "passive"))
      (node (ref "U20") (pin "2") (pinfunction "GND_2") (pintype "passive"))
      (node (ref "U20") (pin "4") (pinfunction "NC_4") (pintype "passive"))
      (node (ref "U25") (pin "1") (pinfunction "GND_1") (pintype "passive"))
      (node (ref "U25") (pin "9") (pinfunction "PAD_9") (pintype "passive"))
      (node (ref "U3") (pin "2") (pinfunction "GND_2") (pintype "passive"))
      (node (ref "U4") (pin "6") (pinfunction "VS-_6") (pintype "power_in"))
      (node (ref "U5") (pin "1") (pinfunction "GND_1") (pintype "passive"))
      (node (ref "U5") (pin "9") (pinfunction "PAD_9") (pintype "passive"))
      (node (ref "U6") (pin "6") (pinfunction "VS-_6") (pintype "power_in"))
      (node (ref "U8") (pin "6") (pinfunction "GND_6") (pintype "passive"))
    )
    (net (code "28") (name "Net-(U2-DIV)") (class "Default")
      (node (ref "R20") (pin "2") (pinfunction "2_2") (pintype "passive"))
      (node (ref "R22") (pin "1") (pinfunction "1_1") (pintype "passive"))
      (node (ref "U2") (pin "4") (pinfunction "DIV_4") (pintype "passive"))
    )
    (net (code "29") (name "Net-(U2-MOD)") (class "Default")
      (node (ref "C5") (pin "2") (pinfunction "2_2") (pintype "passive"))
      (node (ref "R10") (pin "1") (pinfunction "1_1") (pintype "passive"))
      (node (ref "R17") (pin "1") (pinfunction "1_1") (pintype "passive"))
      (node (ref "U2") (pin "1") (pinfunction "MOD_1") (pintype "passive"))
    )
    (net (code "30") (name "Net-(U2-SET)") (class "Default")
      (node (ref "R12") (pin "2") (pinfunction "2_2") (pintype "passive"))
      (node (ref "U2") (pin "3") (pinfunction "SET_3") (pintype "passive"))
    )
    (net (code "31") (name "Net-(U3-DIV)") (class "Default")
      (node (ref "R21") (pin "2") (pinfunction "2_2") (pintype "passive"))
      (node (ref "R23") (pin "1") (pinfunction "1_1") (pintype "passive"))
      (node (ref "U3") (pin "4") (pinfunction "DIV_4") (pintype "passive"))
    )
    (net (code "32") (name "Net-(U3-MOD)") (class "Default")
      (node (ref "C6") (pin "2") (pinfunction "2_2") (pintype "passive"))
      (node (ref "R11") (pin "1") (pinfunction "1_1") (pintype "passive"))
      (node (ref "R19") (pin "1") (pinfunction "1_1") (pintype "passive"))
      (node (ref "U3") (pin "1") (pinfunction "MOD_1") (pintype "passive"))
    )
    (net (code "33") (name "Net-(U3-SET)") (class "Default")
      (node (ref "R13") (pin "2") (pinfunction "2_2") (pintype "passive"))
      (node (ref "U3") (pin "3") (pinfunction "SET_3") (pintype "passive"))
    )
    (net (code "34") (name "Net-(U4-VIN+)") (class "Default")
      (node (ref "C18") (pin "2") (pinfunction "2_2") (pintype "passive"))
      (node (ref "C20") (pin "2") (pinfunction "2_2") (pintype "passive"))
      (node (ref "R36") (pin "2") (pinfunction "2_2") (pintype "passive"))
      (node (ref "R37") (pin "1") (pinfunction "1_1") (pintype "passive"))
      (node (ref "R45") (pin "2") (pinfunction "2_2") (pintype "passive"))
      (node (ref "R46") (pin "1") (pinfunction "1_1") (pintype "passive"))
      (node (ref "U4") (pin "8") (pinfunction "VIN+_8") (pintype "input"))
    )
    (net (code "35") (name "Net-(U4-VIN-)") (class "Default")
      (node (ref "C17") (pin "2") (pinfunction "2_2") (pintype "passive"))
      (node (ref "R34") (pin "1") (pinfunction "1_1") (pintype "passive"))
      (node (ref "R35") (pin "2") (pinfunction "2_2") (pintype "passive"))
      (node (ref "R40") (pin "2") (pinfunction "2_2") (pintype "passive"))
      (node (ref "R41") (pin "1") (pinfunction "1_1") (pintype "passive"))
      (node (ref "U4") (pin "1") (pinfunction "VIN-_1") (pintype "input"))
    )
    (net (code "36") (name "Net-(U5-SENSE1)") (class "Default")
      (node (ref "R24") (pin "2") (pinfunction "2_2") (pintype "passive"))
      (node (ref "U5") (pin "2") (pinfunction "SENSE1_2") (pintype "passive"))
    )
    (net (code "37") (name "Net-(U5-SENSE2)") (class "Default")
      (node (ref "R26") (pin "2") (pinfunction "2_2") (pintype "passive"))
      (node (ref "U5") (pin "3") (pinfunction "SENSE2_3") (pintype "passive"))
    )
    (net (code "38") (name "Net-(U5-TRIP_TEST)") (class "Default")
      (node (ref "J8") (pin "1") (pinfunction "1_1") (pintype "passive"))
      (node (ref "R16") (pin "1") (pinfunction "1_1") (pintype "passive"))
      (node (ref "U5") (pin "5") (pinfunction "TRIP_TEST_5") (pintype "passive"))
    )
    (net (code "39") (name "Net-(U5-VTEMP)") (class "Default")
      (node (ref "R17") (pin "2") (pinfunction "2_2") (pintype "passive"))
      (node (ref "U5") (pin "8") (pinfunction "VTEMP_8") (pintype "passive"))
    )
    (net (code "40") (name "Net-(U6-VIN+)") (class "Default")
      (node (ref "C15") (pin "2") (pinfunction "2_2") (pintype "passive"))
      (node (ref "R32") (pin "2") (pinfunction "2_2") (pintype "passive"))
      (node (ref "R38") (pin "1") (pinfunction "1_1") (pintype "passive"))
      (node (ref "U6") (pin "8") (pinfunction "VIN+_8") (pintype "input"))
    )
    (net (code "41") (name "Net-(U6-VIN-)") (class "Default")
      (node (ref "C16") (pin "2") (pinfunction "2_2") (pintype "passive"))
      (node (ref "R33") (pin "2") (pinfunction "2_2") (pintype "passive"))
      (node (ref "R39") (pin "1") (pinfunction "1_1") (pintype "passive"))
      (node (ref "U6") (pin "1") (pinfunction "VIN-_1") (pintype "input"))
    )
    (net (code "42") (name "Net-(U8-CIP)") (class "Default")
      (node (ref "R47") (pin "1") (pinfunction "1_1") (pintype "passive"))
      (node (ref "R48") (pin "2") (pinfunction "2_2") (pintype "passive"))
      (node (ref "U8") (pin "7") (pinfunction "CIP_7") (pintype "passive"))
    )
    (net (code "43") (name "Net-(U8-COP)") (class "Default")
      (node (ref "R43") (pin "2") (pinfunction "2_2") (pintype "passive"))
      (node (ref "U8") (pin "2") (pinfunction "COP_2") (pintype "passive"))
    )
    (net (code "44") (name "Net-(U8-OUT)") (class "Default")
      (node (ref "R91") (pin "2") (pinfunction "2_2") (pintype "passive"))
      (node (ref "U8") (pin "4") (pinfunction "OUT_4") (pintype "passive"))
    )
    (net (code "45") (name "Net-(U8-REF)") (class "Default")
      (node (ref "R93") (pin "1") (pinfunction "1_1") (pintype "passive"))
      (node (ref "U8") (pin "5") (pinfunction "REF_5") (pintype "passive"))
    )
    (net (code "46") (name "Net-(U20-OUT)") (class "Default")
      (node (ref "R92") (pin "1") (pinfunction "1_1") (pintype "passive"))
      (node (ref "U20") (pin "5") (pinfunction "OUT_5") (pintype "passive"))
    )
    (net (code "47") (name "Net-(U25-SENSE1)") (class "Default")
      (node (ref "R25") (pin "2") (pinfunction "2_2") (pintype "passive"))
      (node (ref "U25") (pin "2") (pinfunction "SENSE1_2") (pintype "passive"))
    )
    (net (code "48") (name "Net-(U25-SENSE2)") (class "Default")
      (node (ref "R27") (pin "2") (pinfunction "2_2") (pintype "passive"))
      (node (ref "U25") (pin "3") (pinfunction "SENSE2_3") (pintype "passive"))
    )
    (net (code "49") (name "Net-(U25-TRIP_TEST)") (class "Default")
      (node (ref "J9") (pin "1") (pinfunction "1_1") (pintype "passive"))
      (node (ref "R18") (pin "1") (pinfunction "1_1") (pintype "passive"))
      (node (ref "U25") (pin "5") (pinfunction "TRIP_TEST_5") (pintype "passive"))
    )
    (net (code "50") (name "Net-(U25-VTEMP)") (class "Default")
      (node (ref "R19") (pin "2") (pinfunction "2_2") (pintype "passive"))
      (node (ref "U25") (pin "8") (pinfunction "VTEMP_8") (pintype "passive"))
    )
    (net (code "51") (name "unconnected-(U5-TOVER-Pad7)") (class "Default")
      (node (ref "U5") (pin "7") (pinfunction "TOVER_7") (pintype "passive+no_connect"))
    )
    (net (code "52") (name "unconnected-(U25-TOVER-Pad7)") (class "Default")
      (node (ref "U25") (pin "7") (pinfunction "TOVER_7") (pintype "passive+no_connect"))
    )
  )
)
